# 10_-_Latching_Delay.net
KiCad netlist of a schematic drawn in Altium Designer
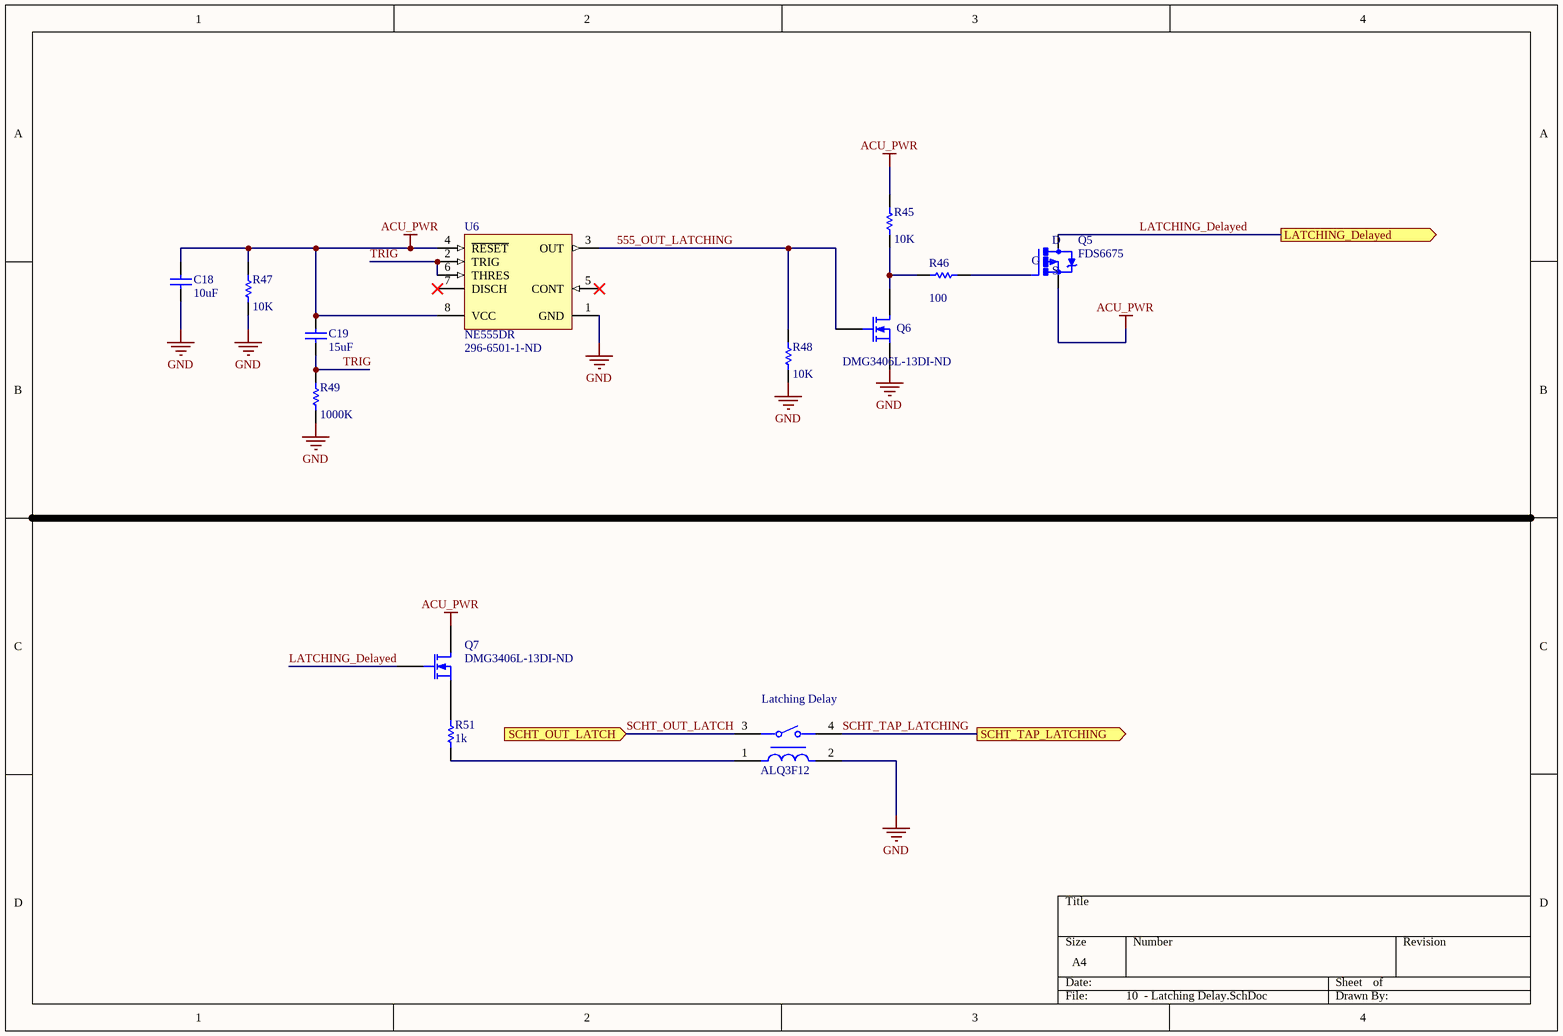
[diagram p0: 10  - Latching Delay.SchDoc]

(export (version "E")
  (design (tool "Eeschema 10.0.6"))
  (components
    (comp (ref "C18")
      (value "10uF")
      (footprint "1608[0603]")
      (description "Capacitor (Semiconductor SIM Model)")
      (fields (field (name "Comment") "Cap Semi") (field (name "PUBLISHER") "Altium Limited"))
      (libsource (lib "Miscellaneous Devices") (part "Cap Semi"))
    )
    (comp (ref "C19")
      (value "15uF")
      (footprint "1608[0603]")
      (description "Capacitor (Semiconductor SIM Model)")
      (fields (field (name "Comment") "Cap Semi") (field (name "PUBLISHER") "Altium Limited"))
      (libsource (lib "Miscellaneous Devices") (part "Cap Semi"))
    )
    (comp (ref "Latching Delay")
      (value "ALQ3F12")
      (footprint "FP-ALQ3F12-MFG")
      (description "ALQ3F12 ALQ Series SPST 10 A 12 V PC Pin Through Hole Class F Insulation Power Relay")
      (libsource (lib "Altium Content Vault") (part "2840b51c2ee6fc134cbdaaad6983ecf"))
    )
    (comp (ref "Q5")
      (value "FDS6675")
      (footprint "SO08-E3")
      (description "P-Channel 30V 11A _Ta_ 2.5W _Ta_ Surface Mount 8-SOIC")
      (fields (field (name "MF") "ON Semiconductor"))
      (libsource (lib "SnapEDAsch") (part "FDS6675"))
    )
    (comp (ref "Q6")
      (value "~")
      (footprint "SOT-23_N")
      (description "N-Channel MOSFET")
      (fields
        (field (name "MANUFACTURER") "Infineon Technologies")
        (field (name "MANUFACTURER PART NUMBER") "IPD075N03L G")
        (field (name "SUPPLIER PART NUMBER 1") "DMG3406L-13DI-ND")
        (field (name "PUBLISHER") "Altium Limited")
      )
      (libsource (lib "Miscellaneous Devices") (part "MOSFET-N"))
    )
    (comp (ref "Q7")
      (value "~")
      (footprint "SOT-23_N")
      (description "N-Channel MOSFET")
      (fields
        (field (name "MANUFACTURER") "Infineon Technologies")
        (field (name "MANUFACTURER PART NUMBER") "IPD075N03L G")
        (field (name "SUPPLIER PART NUMBER 1") "DMG3406L-13DI-ND")
        (field (name "PUBLISHER") "Altium Limited")
      )
      (libsource (lib "Miscellaneous Devices") (part "MOSFET-N"))
    )
    (comp (ref "R45")
      (value "10K")
      (footprint "1608[0603]")
      (description "RES SMD 10K OHM 5% 1/4W 0603")
      (fields
        (field (name "MANUFACTURER") "Rohm Semiconductor")
        (field (name "MANUFACTURER PART NUMBER") "ESR03EZPJ103")
        (field (name "PUBLISHER") "Altium Limited")
      )
      (libsource (lib "Miscellaneous Devices") (part "Res1"))
    )
    (comp (ref "R46")
      (value "100")
      (footprint "1608[0603]")
      (description "RES SMD 100 OHM 5% 1/4W 0603")
      (fields
        (field (name "MANUFACTURER") "Rohm Semiconductor")
        (field (name "MANUFACTURER PART NUMBER") "ESR03EZPJ101")
        (field (name "PUBLISHER") "Altium Limited")
      )
      (libsource (lib "Miscellaneous Devices") (part "Res1"))
    )
    (comp (ref "R47")
      (value "10K")
      (footprint "1608[0603]")
      (description "RES SMD 10K OHM 5% 1/4W 0603")
      (fields
        (field (name "MANUFACTURER") "Rohm Semiconductor")
        (field (name "MANUFACTURER PART NUMBER") "ESR03EZPJ103")
        (field (name "PUBLISHER") "Altium Limited")
      )
      (libsource (lib "Miscellaneous Devices") (part "Res1"))
    )
    (comp (ref "R48")
      (value "10K")
      (footprint "1608[0603]")
      (description "RES SMD 10K OHM 5% 1/4W 0603")
      (fields
        (field (name "MANUFACTURER") "Rohm Semiconductor")
        (field (name "MANUFACTURER PART NUMBER") "ESR03EZPJ103")
        (field (name "PUBLISHER") "Altium Limited")
      )
      (libsource (lib "Miscellaneous Devices") (part "Res1"))
    )
    (comp (ref "R49")
      (value "1000K")
      (footprint "1608[0603]")
      (description "RES SMD 33K OHM 5% 1/4W 0603")
      (fields
        (field (name "MANUFACTURER") "Rohm Semiconductor")
        (field (name "MANUFACTURER PART NUMBER") "ESR03EZPJ333")
        (field (name "PUBLISHER") "Altium Limited")
      )
      (libsource (lib "Miscellaneous Devices") (part "Res1"))
    )
    (comp (ref "R51")
      (value "1k")
      (footprint "1608[0603]")
      (description "RES SMD 100 OHM 5% 1/4W 0603")
      (fields
        (field (name "MANUFACTURER") "Rohm Semiconductor")
        (field (name "MANUFACTURER PART NUMBER") "ESR03EZPJ101")
        (field (name "PUBLISHER") "Altium Limited")
      )
      (libsource (lib "Miscellaneous Devices") (part "Res1"))
    )
    (comp (ref "U6")
      (value "NE555DR")
      (footprint "D0008A_M")
      (fields (field (name "SUPPLIER PART NUMBER 1") "296-6501-1-ND"))
      (libsource (lib "Altium Content Vault") (part "CMP-1685-00007-1"))
    )
  )
  (nets
    (net (code "1") (name "/555_OUT_LATCHING") (class "Default")
      (node (ref "Q6") (pin "1") (pinfunction "G_1") (pintype "passive"))
      (node (ref "R48") (pin "2") (pinfunction "2_2") (pintype "passive"))
      (node (ref "U6") (pin "3") (pinfunction "OUT_3") (pintype "output"))
    )
    (net (code "2") (name "/LATCHING_Delayed") (class "Default")
      (node (ref "Q5") (pin "5-8") (pinfunction "D_5-8") (pintype "passive"))
      (node (ref "Q7") (pin "1") (pinfunction "G_1") (pintype "passive"))
    )
    (net (code "3") (name "/SCHT_OUT_LATCH") (class "Default")
      (node (ref "Latching Delay") (pin "3") (pinfunction "3_3") (pintype "passive"))
    )
    (net (code "4") (name "/SCHT_TAP_LATCHING") (class "Default")
      (node (ref "Latching Delay") (pin "4") (pinfunction "4_4") (pintype "passive"))
    )
    (net (code "5") (name "/TRIG") (class "Default")
      (node (ref "C19") (pin "1") (pinfunction "1_1") (pintype "passive"))
      (node (ref "R49") (pin "2") (pinfunction "2_2") (pintype "passive"))
      (node (ref "U6") (pin "2") (pinfunction "TRIG_2") (pintype "input"))
      (node (ref "U6") (pin "6") (pinfunction "THRES_6") (pintype "input"))
    )
    (net (code "6") (name "ACU_PWR") (class "Default")
      (node (ref "C18") (pin "2") (pinfunction "2_2") (pintype "passive"))
      (node (ref "C19") (pin "2") (pinfunction "2_2") (pintype "passive"))
      (node (ref "Q5") (pin "1-3") (pinfunction "S_1-3") (pintype "passive"))
      (node (ref "Q7") (pin "3") (pinfunction "D_3") (pintype "passive"))
      (node (ref "R45") (pin "2") (pinfunction "2_2") (pintype "passive"))
      (node (ref "R47") (pin "2") (pinfunction "2_2") (pintype "passive"))
      (node (ref "U6") (pin "4") (pinfunction "~{RESET}_4") (pintype "input"))
      (node (ref "U6") (pin "8") (pinfunction "VCC_8") (pintype "power_in"))
    )
    (net (code "7") (name "GND") (class "Default")
      (node (ref "C18") (pin "1") (pinfunction "1_1") (pintype "passive"))
      (node (ref "Latching Delay") (pin "2") (pinfunction "2_2") (pintype "passive"))
      (node (ref "Q6") (pin "2") (pinfunction "S_2") (pintype "passive"))
      (node (ref "R47") (pin "1") (pinfunction "1_1") (pintype "passive"))
      (node (ref "R48") (pin "1") (pinfunction "1_1") (pintype "passive"))
      (node (ref "R49") (pin "1") (pinfunction "1_1") (pintype "passive"))
      (node (ref "U6") (pin "1") (pinfunction "GND_1") (pintype "power_in"))
    )
    (net (code "8") (name "Net-(Latching Delay-Pad1)") (class "Default")
      (node (ref "Latching Delay") (pin "1") (pinfunction "1_1") (pintype "passive"))
      (node (ref "R51") (pin "2") (pinfunction "2_2") (pintype "passive"))
    )
    (net (code "9") (name "Net-(Q5-G)") (class "Default")
      (node (ref "Q5") (pin "4") (pinfunction "G_4") (pintype "passive"))
      (node (ref "R46") (pin "2") (pinfunction "2_2") (pintype "passive"))
    )
    (net (code "10") (name "Net-(Q6-D)") (class "Default")
      (node (ref "Q6") (pin "3") (pinfunction "D_3") (pintype "passive"))
      (node (ref "R45") (pin "1") (pinfunction "1_1") (pintype "passive"))
      (node (ref "R46") (pin "1") (pinfunction "1_1") (pintype "passive"))
    )
    (net (code "11") (name "Net-(Q7-S)") (class "Default")
      (node (ref "Q7") (pin "2") (pinfunction "S_2") (pintype "passive"))
      (node (ref "R51") (pin "1") (pinfunction "1_1") (pintype "passive"))
    )
    (net (code "12") (name "unconnected-(U6-CONT-Pad5)") (class "Default")
      (node (ref "U6") (pin "5") (pinfunction "CONT_5") (pintype "input+no_connect"))
    )
    (net (code "13") (name "unconnected-(U6-DISCH-Pad7)") (class "Default")
      (node (ref "U6") (pin "7") (pinfunction "DISCH_7") (pintype "open_collector+no_connect"))
    )
  )
)
